# 7-segment_mega.net
KiCad netlist of a schematic drawn in EAGLE
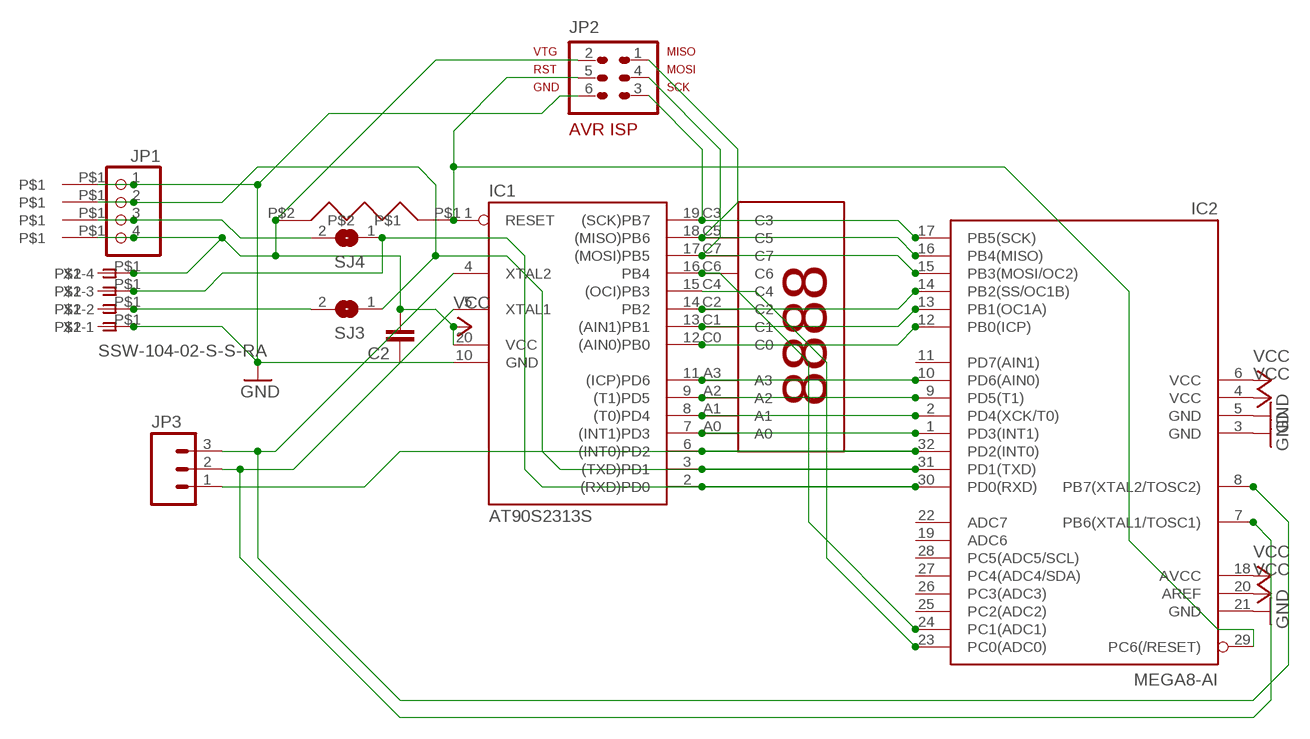
[diagram p0: schematic, sheet 1]

(export (version "E")
  (design (tool "Eeschema 10.0.6"))
  (components
    (comp (ref "C2")
      (value "CAPPTH")
      (footprint "eagle-import:CAP-PTH-SMALL")
      (libsource (lib "eagle-import") (part "CAPPTH"))
    )
    (comp (ref "IC1")
      (value "AT90S2313S")
      (footprint "eagle-import:SO20L")
      (libsource (lib "eagle-import") (part "AT90S2313S"))
    )
    (comp (ref "IC2")
      (value "MEGA8-AI")
      (footprint "eagle-import:TQFP32-08")
      (fields (field (name "MPN") "ATMEGA8-16AU"))
      (libsource (lib "eagle-import") (part "MEGA8-AI"))
    )
    (comp (ref "JP1")
      (value "PINHD-1X4/90")
      (footprint "eagle-import:1X04_90")
      (libsource (lib "eagle-import") (part "PINHD-1X4/90"))
    )
    (comp (ref "JP2")
      (value "AVR-ISP-6")
      (footprint "eagle-import:AVR-ISP-6")
      (libsource (lib "eagle-import") (part "AVR-ISP-6"))
    )
    (comp (ref "JP3")
      (value "M03PTH")
      (footprint "eagle-import:1X03")
      (libsource (lib "eagle-import") (part "M03PTH"))
    )
    (comp (ref "SJ3") (value "SJ") (footprint "eagle-import:SJ") (libsource (lib "eagle-import") (part "SJ")))
    (comp (ref "SJ4") (value "SJ") (footprint "eagle-import:SJ") (libsource (lib "eagle-import") (part "SJ")))
    (comp (ref "U$1")
      (value "7-SEGMENT-DISPLAY-5462-BS")
      (footprint "eagle-import:7SEG_5462BS")
      (libsource (lib "eagle-import") (part "7-SEGMENT-DISPLAY-5462-BS"))
    )
    (comp (ref "U$2")
      (value "R-6")
      (footprint "eagle-import:R-6")
      (libsource (lib "eagle-import") (part "R-6"))
    )
    (comp (ref "U$3")
      (value "WIREPAD_SQUARE_1")
      (footprint "eagle-import:WIREPAD_SQUARE_1")
      (libsource (lib "eagle-import") (part "WIREPAD_SQUARE_1"))
    )
    (comp (ref "U$4")
      (value "WIREPAD_SQUARE_1")
      (footprint "eagle-import:WIREPAD_SQUARE_1")
      (libsource (lib "eagle-import") (part "WIREPAD_SQUARE_1"))
    )
    (comp (ref "U$5")
      (value "WIREPAD_SQUARE_1")
      (footprint "eagle-import:WIREPAD_SQUARE_1")
      (libsource (lib "eagle-import") (part "WIREPAD_SQUARE_1"))
    )
    (comp (ref "U$6")
      (value "WIREPAD_SQUARE_1")
      (footprint "eagle-import:WIREPAD_SQUARE_1")
      (libsource (lib "eagle-import") (part "WIREPAD_SQUARE_1"))
    )
    (comp (ref "U$7")
      (value "WIREPAD_SQUARE_1")
      (footprint "eagle-import:WIREPAD_SQUARE_1")
      (libsource (lib "eagle-import") (part "WIREPAD_SQUARE_1"))
    )
    (comp (ref "U$8")
      (value "WIREPAD_SQUARE_1")
      (footprint "eagle-import:WIREPAD_SQUARE_1")
      (libsource (lib "eagle-import") (part "WIREPAD_SQUARE_1"))
    )
    (comp (ref "U$9")
      (value "WIREPAD_SQUARE_1")
      (footprint "eagle-import:WIREPAD_SQUARE_1")
      (libsource (lib "eagle-import") (part "WIREPAD_SQUARE_1"))
    )
    (comp (ref "U$10")
      (value "WIREPAD_SQUARE_1")
      (footprint "eagle-import:WIREPAD_SQUARE_1")
      (libsource (lib "eagle-import") (part "WIREPAD_SQUARE_1"))
    )
    (comp (ref "X2")
      (value "SSW-104-02-S-S-RA")
      (footprint "eagle-import:SSW-104-02-S-S-RA")
      (libsource (lib "eagle-import") (part "SSW-104-02-S-S-RA"))
    )
  )
  (nets
    (net (code "1") (name "GND") (class "Default")
      (node (ref "C2") (pin "1") (pinfunction "1_1") (pintype "passive"))
      (node (ref "IC1") (pin "10") (pinfunction "GND_10") (pintype "power_in"))
      (node (ref "IC2") (pin "21") (pinfunction "GND_21") (pintype "power_in"))
      (node (ref "IC2") (pin "3") (pinfunction "GND_3") (pintype "power_in"))
      (node (ref "IC2") (pin "5") (pinfunction "GND_5") (pintype "power_in"))
      (node (ref "JP1") (pin "1") (pinfunction "1_1") (pintype "passive"))
      (node (ref "JP2") (pin "6") (pinfunction "6_6") (pintype "passive"))
      (node (ref "U$10") (pin "P$1") (pinfunction "P$1_P$1") (pintype "bidirectional"))
      (node (ref "U$3") (pin "P$1") (pinfunction "P$1_P$1") (pintype "bidirectional"))
      (node (ref "X2") (pin "1") (pinfunction "1_1") (pintype "passive"))
    )
    (net (code "2") (name "Net-(IC1-(AIN0)PB0)") (class "Default")
      (node (ref "IC1") (pin "12") (pinfunction "(AIN0)PB0_12") (pintype "bidirectional"))
      (node (ref "IC2") (pin "12") (pinfunction "PB0(ICP)_12") (pintype "bidirectional"))
      (node (ref "U$1") (pin "C0") (pinfunction "C0_C0") (pintype "bidirectional"))
    )
    (net (code "3") (name "Net-(IC1-(AIN1)PB1)") (class "Default")
      (node (ref "IC1") (pin "13") (pinfunction "(AIN1)PB1_13") (pintype "bidirectional"))
      (node (ref "IC2") (pin "13") (pinfunction "PB1(OC1A)_13") (pintype "bidirectional"))
      (node (ref "U$1") (pin "C1") (pinfunction "C1_C1") (pintype "bidirectional"))
    )
    (net (code "4") (name "Net-(IC1-(ICP)PD6)") (class "Default")
      (node (ref "IC1") (pin "11") (pinfunction "(ICP)PD6_11") (pintype "bidirectional"))
      (node (ref "IC2") (pin "10") (pinfunction "PD6(AIN0)_10") (pintype "bidirectional"))
      (node (ref "U$1") (pin "A3") (pinfunction "A3_A3") (pintype "bidirectional"))
    )
    (net (code "5") (name "Net-(IC1-(INT0)PD2)") (class "Default")
      (node (ref "IC1") (pin "6") (pinfunction "(INT0)PD2_6") (pintype "bidirectional"))
      (node (ref "IC2") (pin "32") (pinfunction "PD2(INT0)_32") (pintype "bidirectional"))
      (node (ref "JP3") (pin "1") (pinfunction "1_1") (pintype "passive"))
    )
    (net (code "6") (name "Net-(IC1-(INT1)PD3)") (class "Default")
      (node (ref "IC1") (pin "7") (pinfunction "(INT1)PD3_7") (pintype "bidirectional"))
      (node (ref "IC2") (pin "1") (pinfunction "PD3(INT1)_1") (pintype "bidirectional"))
      (node (ref "U$1") (pin "A0") (pinfunction "A0_A0") (pintype "bidirectional"))
    )
    (net (code "7") (name "Net-(IC1-(MISO)PB6)") (class "Default")
      (node (ref "IC1") (pin "18") (pinfunction "(MISO)PB6_18") (pintype "bidirectional"))
      (node (ref "IC2") (pin "16") (pinfunction "PB4(MISO)_16") (pintype "bidirectional"))
      (node (ref "JP2") (pin "1") (pinfunction "1_1") (pintype "passive"))
      (node (ref "U$1") (pin "C5") (pinfunction "C5_C5") (pintype "bidirectional"))
    )
    (net (code "8") (name "Net-(IC1-(MOSI)PB5)") (class "Default")
      (node (ref "IC1") (pin "17") (pinfunction "(MOSI)PB5_17") (pintype "bidirectional"))
      (node (ref "IC2") (pin "15") (pinfunction "PB3(MOSI/OC2)_15") (pintype "bidirectional"))
      (node (ref "JP2") (pin "4") (pinfunction "4_4") (pintype "passive"))
      (node (ref "U$1") (pin "C7") (pinfunction "C7_C7") (pintype "bidirectional"))
    )
    (net (code "9") (name "Net-(IC1-(OCI)PB3)") (class "Default")
      (node (ref "IC1") (pin "15") (pinfunction "(OCI)PB3_15") (pintype "bidirectional"))
      (node (ref "IC2") (pin "23") (pinfunction "PC0(ADC0)_23") (pintype "bidirectional"))
      (node (ref "U$1") (pin "C4") (pinfunction "C4_C4") (pintype "bidirectional"))
    )
    (net (code "10") (name "Net-(IC1-(RXD)PD0)") (class "Default")
      (node (ref "IC1") (pin "2") (pinfunction "(RXD)PD0_2") (pintype "bidirectional"))
      (node (ref "IC2") (pin "30") (pinfunction "PD0(RXD)_30") (pintype "bidirectional"))
      (node (ref "SJ4") (pin "1") (pinfunction "1_1") (pintype "passive"))
      (node (ref "U$8") (pin "P$1") (pinfunction "P$1_P$1") (pintype "bidirectional"))
      (node (ref "X2") (pin "3") (pinfunction "1_3") (pintype "passive"))
    )
    (net (code "11") (name "Net-(IC1-(SCK)PB7)") (class "Default")
      (node (ref "IC1") (pin "19") (pinfunction "(SCK)PB7_19") (pintype "bidirectional"))
      (node (ref "IC2") (pin "17") (pinfunction "PB5(SCK)_17") (pintype "bidirectional"))
      (node (ref "JP2") (pin "3") (pinfunction "3_3") (pintype "passive"))
      (node (ref "U$1") (pin "C3") (pinfunction "C3_C3") (pintype "bidirectional"))
    )
    (net (code "12") (name "Net-(IC1-(T0)PD4)") (class "Default")
      (node (ref "IC1") (pin "8") (pinfunction "(T0)PD4_8") (pintype "bidirectional"))
      (node (ref "IC2") (pin "2") (pinfunction "PD4(XCK/T0)_2") (pintype "bidirectional"))
      (node (ref "U$1") (pin "A1") (pinfunction "A1_A1") (pintype "bidirectional"))
    )
    (net (code "13") (name "Net-(IC1-(T1)PD5)") (class "Default")
      (node (ref "IC1") (pin "9") (pinfunction "(T1)PD5_9") (pintype "bidirectional"))
      (node (ref "IC2") (pin "9") (pinfunction "PD5(T1)_9") (pintype "bidirectional"))
      (node (ref "U$1") (pin "A2") (pinfunction "A2_A2") (pintype "bidirectional"))
    )
    (net (code "14") (name "Net-(IC1-(TXD)PD1)") (class "Default")
      (node (ref "IC1") (pin "3") (pinfunction "(TXD)PD1_3") (pintype "bidirectional"))
      (node (ref "IC2") (pin "31") (pinfunction "PD1(TXD)_31") (pintype "bidirectional"))
      (node (ref "JP1") (pin "2") (pinfunction "2_2") (pintype "passive"))
      (node (ref "SJ3") (pin "1") (pinfunction "1_1") (pintype "passive"))
      (node (ref "U$4") (pin "P$1") (pinfunction "P$1_P$1") (pintype "bidirectional"))
    )
    (net (code "15") (name "Net-(IC1-PB2)") (class "Default")
      (node (ref "IC1") (pin "14") (pinfunction "PB2_14") (pintype "bidirectional"))
      (node (ref "IC2") (pin "14") (pinfunction "PB2(SS/OC1B)_14") (pintype "bidirectional"))
      (node (ref "U$1") (pin "C2") (pinfunction "C2_C2") (pintype "bidirectional"))
    )
    (net (code "16") (name "Net-(IC1-PB4)") (class "Default")
      (node (ref "IC1") (pin "16") (pinfunction "PB4_16") (pintype "bidirectional"))
      (node (ref "IC2") (pin "24") (pinfunction "PC1(ADC1)_24") (pintype "bidirectional"))
      (node (ref "U$1") (pin "C6") (pinfunction "C6_C6") (pintype "bidirectional"))
    )
    (net (code "17") (name "Net-(IC1-RESET)") (class "Default")
      (node (ref "IC1") (pin "1") (pinfunction "RESET_1") (pintype "bidirectional"))
      (node (ref "IC2") (pin "29") (pinfunction "PC6(/RESET)_29") (pintype "bidirectional"))
      (node (ref "JP2") (pin "5") (pinfunction "5_5") (pintype "passive"))
      (node (ref "U$2") (pin "P$1") (pinfunction "P$1_P$1") (pintype "bidirectional"))
    )
    (net (code "18") (name "Net-(IC1-XTAL1)") (class "Default")
      (node (ref "IC1") (pin "5") (pinfunction "XTAL1_5") (pintype "bidirectional"))
      (node (ref "IC2") (pin "7") (pinfunction "PB6(XTAL1/TOSC1)_7") (pintype "bidirectional"))
      (node (ref "JP3") (pin "2") (pinfunction "2_2") (pintype "passive"))
    )
    (net (code "19") (name "Net-(IC1-XTAL2)") (class "Default")
      (node (ref "IC1") (pin "4") (pinfunction "XTAL2_4") (pintype "bidirectional"))
      (node (ref "IC2") (pin "8") (pinfunction "PB7(XTAL2/TOSC2)_8") (pintype "bidirectional"))
      (node (ref "JP3") (pin "3") (pinfunction "3_3") (pintype "passive"))
    )
    (net (code "20") (name "Net-(JP1-Pad3)") (class "Default")
      (node (ref "JP1") (pin "3") (pinfunction "3_3") (pintype "passive"))
      (node (ref "SJ4") (pin "2") (pinfunction "2_2") (pintype "passive"))
      (node (ref "U$5") (pin "P$1") (pinfunction "P$1_P$1") (pintype "bidirectional"))
    )
    (net (code "21") (name "Net-(X2B-1)") (class "Default")
      (node (ref "SJ3") (pin "2") (pinfunction "2_2") (pintype "passive"))
      (node (ref "U$9") (pin "P$1") (pinfunction "P$1_P$1") (pintype "bidirectional"))
      (node (ref "X2") (pin "2") (pinfunction "1_2") (pintype "passive"))
    )
    (net (code "22") (name "VCC") (class "Default")
      (node (ref "C2") (pin "2") (pinfunction "2_2") (pintype "passive"))
      (node (ref "IC1") (pin "20") (pinfunction "VCC_20") (pintype "power_in"))
      (node (ref "IC2") (pin "18") (pinfunction "AVCC_18") (pintype "power_in"))
      (node (ref "IC2") (pin "20") (pinfunction "AREF_20") (pintype "passive"))
      (node (ref "IC2") (pin "4") (pinfunction "VCC_4") (pintype "power_in"))
      (node (ref "IC2") (pin "6") (pinfunction "VCC_6") (pintype "power_in"))
      (node (ref "JP1") (pin "4") (pinfunction "4_4") (pintype "passive"))
      (node (ref "JP2") (pin "2") (pinfunction "2_2") (pintype "passive"))
      (node (ref "U$2") (pin "P$2") (pinfunction "P$2_P$2") (pintype "bidirectional"))
      (node (ref "U$6") (pin "P$1") (pinfunction "P$1_P$1") (pintype "bidirectional"))
      (node (ref "U$7") (pin "P$1") (pinfunction "P$1_P$1") (pintype "bidirectional"))
      (node (ref "X2") (pin "4") (pinfunction "1_4") (pintype "passive"))
    )
    (net (code "23") (name "unconnected-(IC2-ADC6-Pad19)") (class "Default")
      (node (ref "IC2") (pin "19") (pinfunction "ADC6_19") (pintype "bidirectional"))
    )
    (net (code "24") (name "unconnected-(IC2-ADC7-Pad22)") (class "Default")
      (node (ref "IC2") (pin "22") (pinfunction "ADC7_22") (pintype "bidirectional"))
    )
    (net (code "25") (name "unconnected-(IC2-PC2(ADC2)-Pad25)") (class "Default")
      (node (ref "IC2") (pin "25") (pinfunction "PC2(ADC2)_25") (pintype "bidirectional"))
    )
    (net (code "26") (name "unconnected-(IC2-PC3(ADC3)-Pad26)") (class "Default")
      (node (ref "IC2") (pin "26") (pinfunction "PC3(ADC3)_26") (pintype "bidirectional"))
    )
    (net (code "27") (name "unconnected-(IC2-PC4(ADC4{slash}SDA)-Pad27)") (class "Default")
      (node (ref "IC2") (pin "27") (pinfunction "PC4(ADC4/SDA)_27") (pintype "bidirectional"))
    )
    (net (code "28") (name "unconnected-(IC2-PC5(ADC5{slash}SCL)-Pad28)") (class "Default")
      (node (ref "IC2") (pin "28") (pinfunction "PC5(ADC5/SCL)_28") (pintype "bidirectional"))
    )
    (net (code "29") (name "unconnected-(IC2-PD7(AIN1)-Pad11)") (class "Default")
      (node (ref "IC2") (pin "11") (pinfunction "PD7(AIN1)_11") (pintype "bidirectional"))
    )
  )
)
